# Radio.net
KiCad netlist of a schematic drawn in Altium Designer
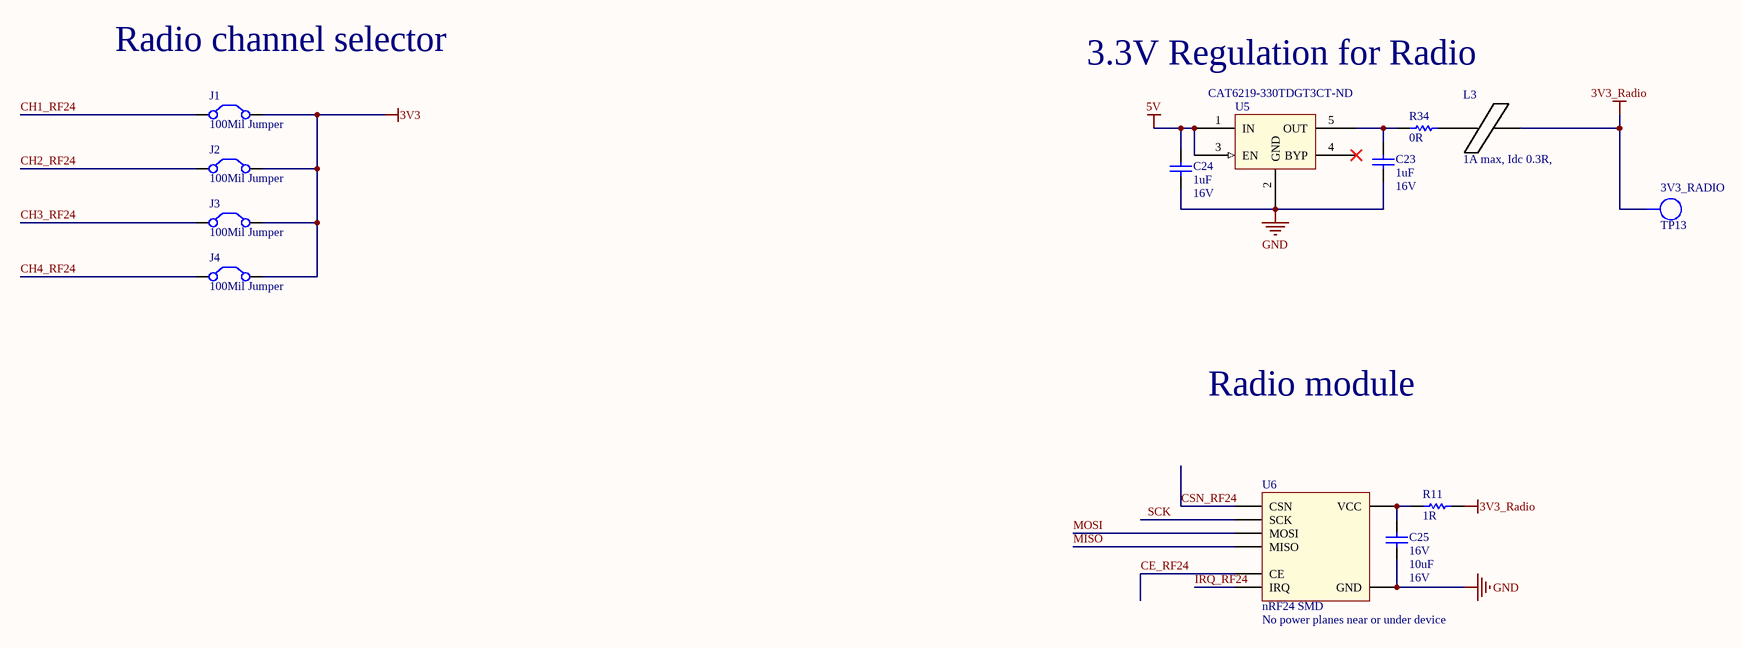
[diagram p0: Radio.SchDoc]

(export (version "E")
  (design (tool "Eeschema 10.0.6"))
  (components
    (comp (ref "C23")
      (value "1uF")
      (footprint "CAPC1608L")
      (description "CAP CER 1uF Y5V -20% +80% 16V 0603")
      (fields (field (name "MAX VOLTAGE") "16V"))
      (libsource (lib "ECE AD19Components_19V1") (part "CC_1uF_0603"))
    )
    (comp (ref "C24")
      (value "1uF")
      (footprint "CAPC1608L")
      (description "CAP CER 1uF Y5V -20% +80% 16V 0603")
      (fields (field (name "MAX VOLTAGE") "16V"))
      (libsource (lib "ECE AD19Components_19V1") (part "CC_1uF_0603"))
    )
    (comp (ref "C25")
      (value "10uF")
      (footprint "CAPC2012L")
      (description "CAP CER 10uF X5R 16V 0805")
      (fields
        (field (name "MANUFACTURER") "Samsung Electro-Mechanics")
        (field (name "MANUFACTURER PART NUMBER") "CL21A106KOQNNWE")
        (field (name "VOLTAGE - RATED") "16V")
        (field (name "MAX VOLTAGE") "16V")
      )
      (libsource (lib "ENCE461AD19_19V2") (part "CC_10uF_16V_0805"))
    )
    (comp (ref "J1")
      (value "100Mil Jumper")
      (footprint "JMP2.54")
      (description "2.54mm Jumper Thru Hole")
      (libsource (lib "ECE AD19Components_19V1") (part "TP_JUMPER"))
    )
    (comp (ref "J2")
      (value "100Mil Jumper")
      (footprint "JMP2.54")
      (description "2.54mm Jumper Thru Hole")
      (libsource (lib "ECE AD19Components_19V1") (part "TP_JUMPER"))
    )
    (comp (ref "J3")
      (value "100Mil Jumper")
      (footprint "JMP2.54")
      (description "2.54mm Jumper Thru Hole")
      (libsource (lib "ECE AD19Components_19V1") (part "TP_JUMPER"))
    )
    (comp (ref "J4")
      (value "100Mil Jumper")
      (footprint "JMP2.54")
      (description "2.54mm Jumper Thru Hole")
      (libsource (lib "ECE AD19Components_19V1") (part "TP_JUMPER"))
    )
    (comp (ref "L3")
      (value "1A max, Idc 0.3R,")
      (footprint "INDC3216L")
      (description "Ferrite Bead, Rdc 0.3R, Z100MHZ 600R, Imax 1A, SMD 1206")
      (fields
        (field (name "MANUFACTURER") "FAIR-RITE")
        (field (name "MANUFACTURER PART NUMBER") "2512066017Y1")
      )
      (libsource (lib "ECE AD19Components_19V1") (part "IN_Ferrite-Bead"))
    )
    (comp (ref "R11")
      (value "1R")
      (footprint "RESC3216L")
      (description "RES 1R OHM 1/4W 5% 1206 SMD")
      (libsource (lib "ECE AD19Components_19V1") (part "RT_1R"))
    )
    (comp (ref "R34")
      (value "0R")
      (footprint "RESC1608L")
      (description "RES 0.0 OHM 1/10W 5% 0603 SMD")
      (libsource (lib "ECE AD19Components_19V1") (part "RS_0R0"))
    )
    (comp (ref "TP13")
      (value "3V3_RADIO")
      (footprint "TP_1206")
      (description "Test-Point 3.3x1.6x2.1mm SMD")
      (fields
        (field (name "MANUFACTURER") "Harwin Inc")
        (field (name "MANUFACTURER PART NUMBER") "S1751-46R")
      )
      (libsource (lib "ECE AD19Components_19V1") (part "TP_1206"))
    )
    (comp (ref "U5")
      (value "CAT6219-330TDGT3")
      (footprint "SOT95P280X145-5N")
      (description "IC REG LIN 3.3V 500MA TSOT23-5")
      (fields
        (field (name "BASE PART NUMBER") "CAT6219")
        (field (name "SUPPLIER PART NUMBER") "CAT6219-330TDGT3CT-ND")
      )
      (libsource (lib "ENCE461AD19_19V2") (part "SV_CAT6219-330TDGT3"))
    )
    (comp (ref "U6")
      (value "nRF24 SMD")
      (footprint "NRF24")
      (description "nRF24 SMD Module")
      (fields (field (name "WARNING") "No power planes near or under device"))
      (libsource (lib "ENCE461AD19_19V2") (part "NRF24"))
    )
  )
  (nets
    (net (code "1") (name "/CE_RF24") (class "Default")
      (node (ref "U6") (pin "3") (pinfunction "CE_3") (pintype "passive"))
    )
    (net (code "2") (name "/CH1_RF24") (class "Default")
      (node (ref "J1") (pin "1") (pinfunction "C1_1") (pintype "passive"))
    )
    (net (code "3") (name "/CH2_RF24") (class "Default")
      (node (ref "J2") (pin "1") (pinfunction "C1_1") (pintype "passive"))
    )
    (net (code "4") (name "/CH3_RF24") (class "Default")
      (node (ref "J3") (pin "1") (pinfunction "C1_1") (pintype "passive"))
    )
    (net (code "5") (name "/CH4_RF24") (class "Default")
      (node (ref "J4") (pin "1") (pinfunction "C1_1") (pintype "passive"))
    )
    (net (code "6") (name "/CSN_RF24") (class "Default")
      (node (ref "U6") (pin "4") (pinfunction "CSN_4") (pintype "passive"))
    )
    (net (code "7") (name "/IRQ_RF24") (class "Default")
      (node (ref "U6") (pin "8") (pinfunction "IRQ_8") (pintype "passive"))
    )
    (net (code "8") (name "/MISO") (class "Default")
      (node (ref "U6") (pin "7") (pinfunction "MISO_7") (pintype "passive"))
    )
    (net (code "9") (name "/MOSI") (class "Default")
      (node (ref "U6") (pin "6") (pinfunction "MOSI_6") (pintype "passive"))
    )
    (net (code "10") (name "/SCK") (class "Default")
      (node (ref "U6") (pin "5") (pinfunction "SCK_5") (pintype "passive"))
    )
    (net (code "11") (name "3V3") (class "Default")
      (node (ref "J1") (pin "2") (pinfunction "C2_2") (pintype "passive"))
      (node (ref "J2") (pin "2") (pinfunction "C2_2") (pintype "passive"))
      (node (ref "J3") (pin "2") (pinfunction "C2_2") (pintype "passive"))
      (node (ref "J4") (pin "2") (pinfunction "C2_2") (pintype "passive"))
    )
    (net (code "12") (name "3V3_Radio") (class "Default")
      (node (ref "L3") (pin "2") (pinfunction "2_2") (pintype "passive"))
      (node (ref "R11") (pin "2") (pinfunction "2_2") (pintype "passive"))
      (node (ref "TP13") (pin "1") (pinfunction "1_1") (pintype "passive"))
    )
    (net (code "13") (name "5V") (class "Default")
      (node (ref "C24") (pin "2") (pinfunction "2_2") (pintype "passive"))
      (node (ref "U5") (pin "1") (pinfunction "IN_1") (pintype "power_in"))
      (node (ref "U5") (pin "3") (pinfunction "EN_3") (pintype "input"))
    )
    (net (code "14") (name "GND") (class "Default")
      (node (ref "C23") (pin "1") (pinfunction "1_1") (pintype "passive"))
      (node (ref "C24") (pin "1") (pinfunction "1_1") (pintype "passive"))
      (node (ref "C25") (pin "1") (pinfunction "1_1") (pintype "passive"))
      (node (ref "U5") (pin "2") (pinfunction "GND_2") (pintype "power_in"))
      (node (ref "U6") (pin "2") (pinfunction "GND_2") (pintype "passive"))
    )
    (net (code "15") (name "Net-(L3-Pad1)") (class "Default")
      (node (ref "L3") (pin "1") (pinfunction "1_1") (pintype "passive"))
      (node (ref "R34") (pin "2") (pinfunction "2_2") (pintype "passive"))
    )
    (net (code "16") (name "Net-(U5-OUT)") (class "Default")
      (node (ref "C23") (pin "2") (pinfunction "2_2") (pintype "passive"))
      (node (ref "R34") (pin "1") (pinfunction "1_1") (pintype "passive"))
      (node (ref "U5") (pin "5") (pinfunction "OUT_5") (pintype "power_in"))
    )
    (net (code "17") (name "Net-(U6-VCC)") (class "Default")
      (node (ref "C25") (pin "2") (pinfunction "2_2") (pintype "passive"))
      (node (ref "R11") (pin "1") (pinfunction "1_1") (pintype "passive"))
      (node (ref "U6") (pin "1") (pinfunction "VCC_1") (pintype "passive"))
    )
    (net (code "18") (name "unconnected-(U5-BYP-Pad4)") (class "Default")
      (node (ref "U5") (pin "4") (pinfunction "BYP_4") (pintype "passive+no_connect"))
    )
  )
)
